# DESIGN7MA.net
KiCad netlist of a schematic drawn in EAGLE
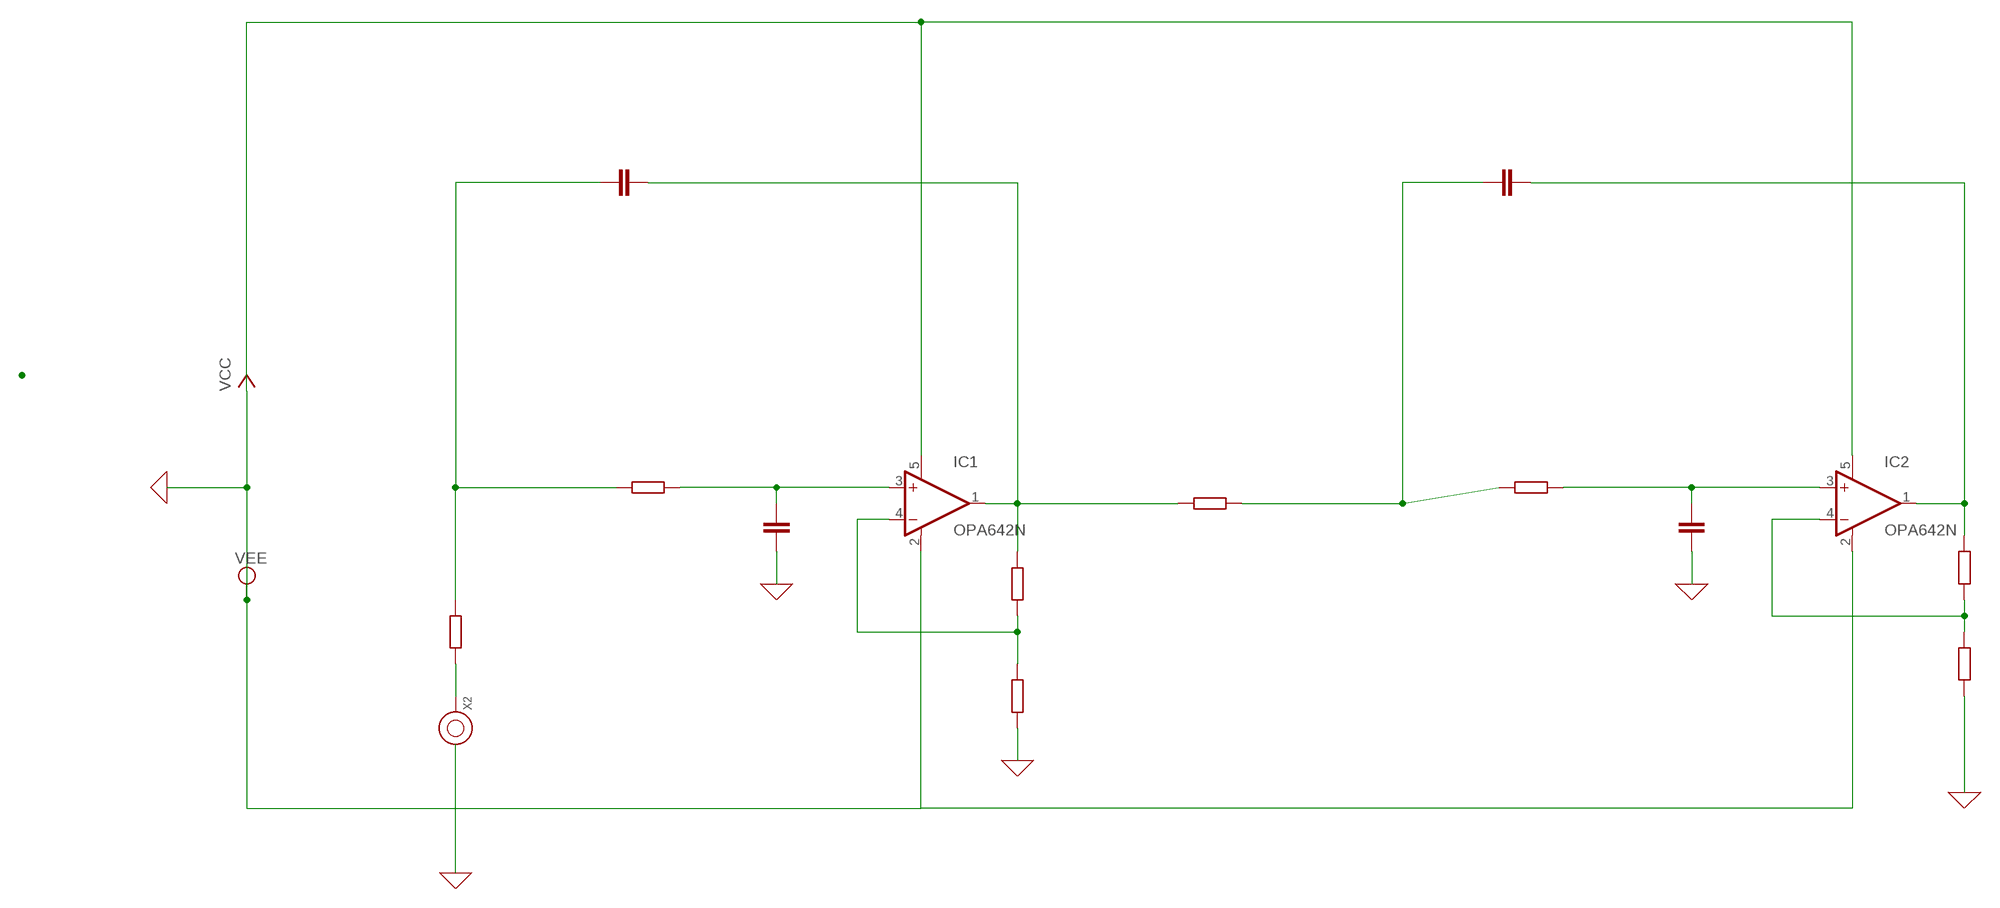
[diagram p0: schematic, sheet 1]

(export (version "E")
  (design (tool "Eeschema 10.0.6"))
  (components
    (comp (ref "IC1")
      (value "OPA642N")
      (footprint "eagle-import:SOT23-5")
      (libsource (lib "eagle-import") (part "OPA642N"))
    )
    (comp (ref "IC2")
      (value "OPA642N")
      (footprint "eagle-import:SOT23-5")
      (libsource (lib "eagle-import") (part "OPA642N"))
    )
    (comp (ref "X2")
      (value "BINDING-POST")
      (footprint "eagle-import:BINDING-POST")
      (libsource (lib "eagle-import") (part "BINDING-POST"))
    )
  )
  (nets
    (net (code "1") (name "GND") (class "Default")
      (node (ref "IC1") (pin "2") (pinfunction "V-_2") (pintype "power_in"))
      (node (ref "IC1") (pin "5") (pinfunction "V+_5") (pintype "power_in"))
      (node (ref "IC2") (pin "2") (pinfunction "V-_2") (pintype "power_in"))
      (node (ref "IC2") (pin "5") (pinfunction "V+_5") (pintype "power_in"))
    )
    (net (code "2") (name "Net-(X2-1-Pad1_1)") (class "Default")
      (node (ref "X2") (pin "1") (pinfunction "1_1") (pintype "passive"))
      (node (ref "X2") (pin "1_1") (pinfunction "1_1_1") (pintype "passive"))
      (node (ref "X2") (pin "1_2") (pinfunction "1_1_2") (pintype "passive"))
      (node (ref "X2") (pin "1_3") (pinfunction "1_1_3") (pintype "passive"))
      (node (ref "X2") (pin "1_4") (pinfunction "1_1_4") (pintype "passive"))
      (node (ref "X2") (pin "1_5") (pinfunction "1_1_5") (pintype "passive"))
      (node (ref "X2") (pin "1_6") (pinfunction "1_1_6") (pintype "passive"))
      (node (ref "X2") (pin "1_7") (pinfunction "1_1_7") (pintype "passive"))
      (node (ref "X2") (pin "1_8") (pinfunction "1_1_8") (pintype "passive"))
    )
    (net (code "3") (name "unconnected-(IC1-+IN-Pad3)") (class "Default")
      (node (ref "IC1") (pin "3") (pinfunction "+IN_3") (pintype "input"))
    )
    (net (code "4") (name "unconnected-(IC1--IN-Pad4)") (class "Default")
      (node (ref "IC1") (pin "4") (pinfunction "-IN_4") (pintype "input"))
    )
    (net (code "5") (name "unconnected-(IC1-OUT-Pad1)") (class "Default")
      (node (ref "IC1") (pin "1") (pinfunction "OUT_1") (pintype "output"))
    )
    (net (code "6") (name "unconnected-(IC2-+IN-Pad3)") (class "Default")
      (node (ref "IC2") (pin "3") (pinfunction "+IN_3") (pintype "input"))
    )
    (net (code "7") (name "unconnected-(IC2--IN-Pad4)") (class "Default")
      (node (ref "IC2") (pin "4") (pinfunction "-IN_4") (pintype "input"))
    )
    (net (code "8") (name "unconnected-(IC2-OUT-Pad1)") (class "Default")
      (node (ref "IC2") (pin "1") (pinfunction "OUT_1") (pintype "output"))
    )
  )
)
